# 1_P3.net
KiCad netlist of a schematic drawn in Altium Designer
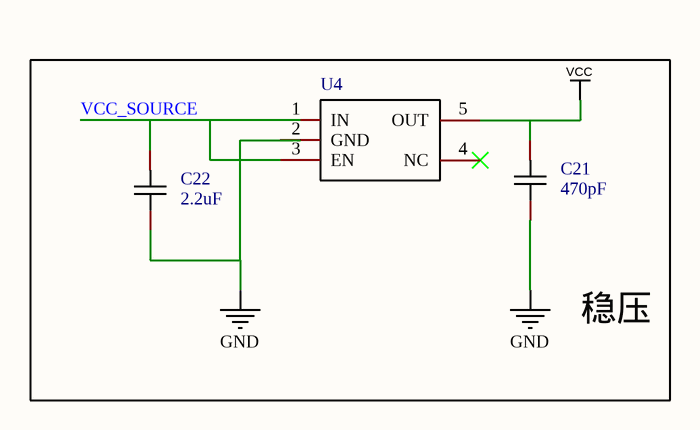
[diagram p0: 1_P3.schdoc]

(export (version "E")
  (design (tool "Eeschema 10.0.6"))
  (components
    (comp (ref "C21")
      (value "470pF")
      (description "温度系数:C0G;精度:±5%;额定电压:50V;容值:47pF;")
      (fields
        (field (name "MANUFACTURER") "muRata(村田)")
        (field (name "MANUFACTURER PART") "GRM0335C1H470JA01D")
      )
      (libsource (lib "altium-import") (part "root_1_GRM0335C1H470JA01D_"))
    )
    (comp (ref "C22")
      (value "2.2uF")
      (description "温度系数:C0G;精度:±5%;额定电压:50V;容值:47pF;")
      (fields
        (field (name "MANUFACTURER") "muRata(村田)")
        (field (name "MANUFACTURER PART") "GRM0335C1H470JA01D")
      )
      (libsource (lib "altium-import") (part "root_1_GRM0335C1H470JA01D_"))
    )
    (comp (ref "U4")
      (value "MIC5203-3.3YM5-TR")
      (description "输出类型:固定;输出极性:正;输出通道数:1;最大输入电压:16V;输出电压:3.3V;压差:600mV@(80mA);输出电流:80mA;电源纹波抑制比(PRSS):-;")
      (fields (field (name "MANUFACTURER") "MICROCHIP(美国微芯)"))
      (libsource (lib "altium-import") (part "root_0_MIC5203-3.3YM5-TR_"))
    )
  )
  (nets
    (net (code "1") (name "/VCC_SOURCE") (class "Default")
      (node (ref "C22") (pin "2") (pinfunction "2_2") (pintype "passive"))
      (node (ref "U4") (pin "1") (pinfunction "IN_1") (pintype "passive"))
      (node (ref "U4") (pin "3") (pinfunction "EN_3") (pintype "passive"))
    )
    (net (code "2") (name "GND") (class "Default")
      (node (ref "C21") (pin "1") (pinfunction "1_1") (pintype "passive"))
      (node (ref "C22") (pin "1") (pinfunction "1_1") (pintype "passive"))
      (node (ref "U4") (pin "2") (pinfunction "GND_2") (pintype "passive"))
    )
    (net (code "3") (name "VCC") (class "Default")
      (node (ref "C21") (pin "2") (pinfunction "2_2") (pintype "passive"))
      (node (ref "U4") (pin "5") (pinfunction "OUT_5") (pintype "passive"))
    )
    (net (code "4") (name "unconnected-(U4-NC-Pad4)") (class "Default")
      (node (ref "U4") (pin "4") (pinfunction "NC_4") (pintype "passive+no_connect"))
    )
  )
)
